# switching_board.net
KiCad netlist of a schematic drawn in Altium Designer
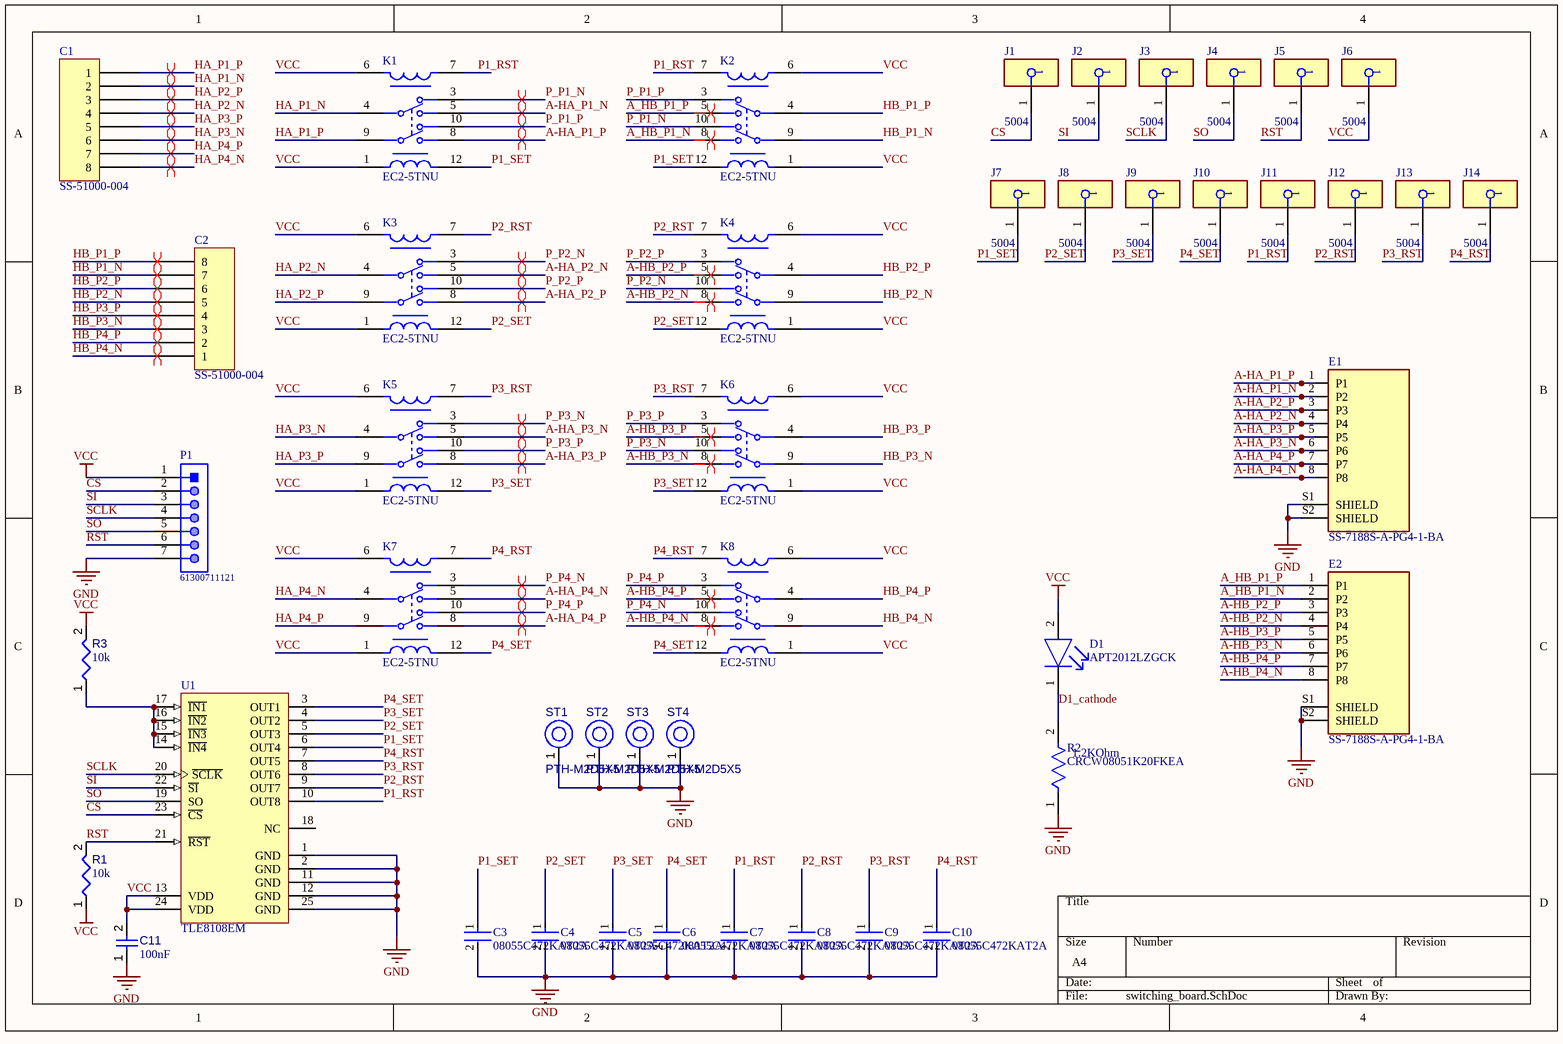
[diagram p0: switching_board.SchDoc]

(export (version "E")
  (design (tool "Eeschema 10.0.6"))
  (components
    (comp (ref "C1")
      (value "SS-51000-004")
      (footprint "SS-51000-004-Footprint-1")
      (description "Stewart Connector, Internal Part #: SS-51000-004")
      (libsource (lib "") (part "SS-51000-004-Symbol-1_1"))
    )
    (comp (ref "C2")
      (value "SS-51000-004")
      (footprint "SS-51000-004-Footprint-1")
      (description "Stewart Connector, Internal Part #: SS-51000-004")
      (libsource (lib "capstone") (part "SS-51000-004-Symbol-1"))
    )
    (comp (ref "C3")
      (value "08055C472KAT2A")
      (footprint "FP-0805-L_2_01_0_2-W_1_25-IPC_B")
      (description "General Purpose Ceramic Capacitor, 0805, 4.7nF, 10%, X7R, 0.15, 50V")
      (fields (field (name "VOLTAGE") "50V") (field (name "TOLERANCE") "10%"))
      (libsource (lib "Altium Content Vault") (part "02cd4be3c70576c341d710602a673aa"))
    )
    (comp (ref "C4")
      (value "08055C472KAT2A")
      (footprint "FP-0805-L_2_01_0_2-W_1_25-IPC_B")
      (description "General Purpose Ceramic Capacitor, 0805, 4.7nF, 10%, X7R, 0.15, 50V")
      (fields (field (name "VOLTAGE") "50V") (field (name "TOLERANCE") "10%"))
      (libsource (lib "Altium Content Vault") (part "02cd4be3c70576c341d710602a673aa"))
    )
    (comp (ref "C5")
      (value "08055C472KAT2A")
      (footprint "FP-0805-L_2_01_0_2-W_1_25-IPC_B")
      (description "General Purpose Ceramic Capacitor, 0805, 4.7nF, 10%, X7R, 0.15, 50V")
      (fields (field (name "VOLTAGE") "50V") (field (name "TOLERANCE") "10%"))
      (libsource (lib "Altium Content Vault") (part "02cd4be3c70576c341d710602a673aa"))
    )
    (comp (ref "C6")
      (value "08055C472KAT2A")
      (footprint "FP-0805-L_2_01_0_2-W_1_25-IPC_B")
      (description "General Purpose Ceramic Capacitor, 0805, 4.7nF, 10%, X7R, 0.15, 50V")
      (fields (field (name "VOLTAGE") "50V") (field (name "TOLERANCE") "10%"))
      (libsource (lib "Altium Content Vault") (part "02cd4be3c70576c341d710602a673aa"))
    )
    (comp (ref "C7")
      (value "08055C472KAT2A")
      (footprint "FP-0805-L_2_01_0_2-W_1_25-IPC_B")
      (description "General Purpose Ceramic Capacitor, 0805, 4.7nF, 10%, X7R, 0.15, 50V")
      (fields (field (name "VOLTAGE") "50V") (field (name "TOLERANCE") "10%"))
      (libsource (lib "Altium Content Vault") (part "02cd4be3c70576c341d710602a673aa"))
    )
    (comp (ref "C8")
      (value "08055C472KAT2A")
      (footprint "FP-0805-L_2_01_0_2-W_1_25-IPC_B")
      (description "General Purpose Ceramic Capacitor, 0805, 4.7nF, 10%, X7R, 0.15, 50V")
      (fields (field (name "VOLTAGE") "50V") (field (name "TOLERANCE") "10%"))
      (libsource (lib "Altium Content Vault") (part "02cd4be3c70576c341d710602a673aa"))
    )
    (comp (ref "C9")
      (value "08055C472KAT2A")
      (footprint "FP-0805-L_2_01_0_2-W_1_25-IPC_B")
      (description "General Purpose Ceramic Capacitor, 0805, 4.7nF, 10%, X7R, 0.15, 50V")
      (fields (field (name "VOLTAGE") "50V") (field (name "TOLERANCE") "10%"))
      (libsource (lib "Altium Content Vault") (part "02cd4be3c70576c341d710602a673aa"))
    )
    (comp (ref "C10")
      (value "08055C472KAT2A")
      (footprint "FP-0805-L_2_01_0_2-W_1_25-IPC_B")
      (description "General Purpose Ceramic Capacitor, 0805, 4.7nF, 10%, X7R, 0.15, 50V")
      (fields (field (name "VOLTAGE") "50V") (field (name "TOLERANCE") "10%"))
      (libsource (lib "Altium Content Vault") (part "02cd4be3c70576c341d710602a673aa"))
    )
    (comp (ref "C11")
      (value "100nF")
      (footprint "CAPC2013X95X50LL10T25")
      (description "Chip Capacitor, 100 nF, +/- 10%, 50 V, 0805 (2012 Metric)")
      (fields (field (name "TOLERANCE") "10%") (field (name "Comment") "Capacitor 100 nF +/-10% 50 V 0805"))
      (libsource (lib "capstone") (part "CAP-NP-2"))
    )
    (comp (ref "D1")
      (value "APT2012LZGCK")
      (footprint "FP-APT2012LZGCK-MFG")
      (description "LED GREEN CLEAR 2SMD")
      (libsource (lib "Altium Content Vault") (part "590121a5bdfd2d28d8ee457b77c7368"))
    )
    (comp (ref "E1")
      (value "SS-7188S-A-PG4-1-BA")
      (footprint "SS-7188S-A-PG4-1-BA-Footprint-1")
      (description "Conn Modular Jack F 8 POS 1.27mm Solder RA Thru-Hole 8 Terminal 1 Port")
      (libsource (lib "capstone") (part "SS-7188S-A-PG4-1-BA-Symbol-1"))
    )
    (comp (ref "E2")
      (value "SS-7188S-A-PG4-1-BA")
      (footprint "SS-7188S-A-PG4-1-BA-Footprint-1")
      (description "Conn Modular Jack F 8 POS 1.27mm Solder RA Thru-Hole 8 Terminal 1 Port")
      (libsource (lib "capstone") (part "SS-7188S-A-PG4-1-BA-Symbol-1"))
    )
    (comp (ref "J1")
      (value "5004")
      (footprint "FP-5004-MFG")
      (description "PC TEST POINT MINIATURE YELLOW")
      (fields
        (field (name "MANUFACTURER") "Keystone")
        (field (name "OCTOPART") "https://octopart.com/5004-keystone-28591")
      )
      (libsource (lib "Altium Content Vault") (part "98815daf2f2c152b0c43f5ab9800df6"))
    )
    (comp (ref "J2")
      (value "5004")
      (footprint "FP-5004-MFG")
      (description "PC TEST POINT MINIATURE YELLOW")
      (fields
        (field (name "MANUFACTURER") "Keystone")
        (field (name "OCTOPART") "https://octopart.com/5004-keystone-28591")
      )
      (libsource (lib "Altium Content Vault") (part "98815daf2f2c152b0c43f5ab9800df6"))
    )
    (comp (ref "J3")
      (value "5004")
      (footprint "FP-5004-MFG")
      (description "PC TEST POINT MINIATURE YELLOW")
      (fields
        (field (name "MANUFACTURER") "Keystone")
        (field (name "OCTOPART") "https://octopart.com/5004-keystone-28591")
      )
      (libsource (lib "Altium Content Vault") (part "98815daf2f2c152b0c43f5ab9800df6"))
    )
    (comp (ref "J4")
      (value "5004")
      (footprint "FP-5004-MFG")
      (description "PC TEST POINT MINIATURE YELLOW")
      (fields
        (field (name "MANUFACTURER") "Keystone")
        (field (name "OCTOPART") "https://octopart.com/5004-keystone-28591")
      )
      (libsource (lib "Altium Content Vault") (part "98815daf2f2c152b0c43f5ab9800df6"))
    )
    (comp (ref "J5")
      (value "5004")
      (footprint "FP-5004-MFG")
      (description "PC TEST POINT MINIATURE YELLOW")
      (fields
        (field (name "MANUFACTURER") "Keystone")
        (field (name "OCTOPART") "https://octopart.com/5004-keystone-28591")
      )
      (libsource (lib "Altium Content Vault") (part "98815daf2f2c152b0c43f5ab9800df6"))
    )
    (comp (ref "J6")
      (value "5004")
      (footprint "FP-5004-MFG")
      (description "PC TEST POINT MINIATURE YELLOW")
      (fields
        (field (name "MANUFACTURER") "Keystone")
        (field (name "OCTOPART") "https://octopart.com/5004-keystone-28591")
      )
      (libsource (lib "Altium Content Vault") (part "98815daf2f2c152b0c43f5ab9800df6"))
    )
    (comp (ref "J7")
      (value "5004")
      (footprint "FP-5004-MFG")
      (description "PC TEST POINT MINIATURE YELLOW")
      (fields
        (field (name "MANUFACTURER") "Keystone")
        (field (name "OCTOPART") "https://octopart.com/5004-keystone-28591")
      )
      (libsource (lib "Altium Content Vault") (part "98815daf2f2c152b0c43f5ab9800df6"))
    )
    (comp (ref "J8")
      (value "5004")
      (footprint "FP-5004-MFG")
      (description "PC TEST POINT MINIATURE YELLOW")
      (fields
        (field (name "MANUFACTURER") "Keystone")
        (field (name "OCTOPART") "https://octopart.com/5004-keystone-28591")
      )
      (libsource (lib "Altium Content Vault") (part "98815daf2f2c152b0c43f5ab9800df6"))
    )
    (comp (ref "J9")
      (value "5004")
      (footprint "FP-5004-MFG")
      (description "PC TEST POINT MINIATURE YELLOW")
      (fields
        (field (name "MANUFACTURER") "Keystone")
        (field (name "OCTOPART") "https://octopart.com/5004-keystone-28591")
      )
      (libsource (lib "Altium Content Vault") (part "98815daf2f2c152b0c43f5ab9800df6"))
    )
    (comp (ref "J10")
      (value "5004")
      (footprint "FP-5004-MFG")
      (description "PC TEST POINT MINIATURE YELLOW")
      (fields
        (field (name "MANUFACTURER") "Keystone")
        (field (name "OCTOPART") "https://octopart.com/5004-keystone-28591")
      )
      (libsource (lib "Altium Content Vault") (part "98815daf2f2c152b0c43f5ab9800df6"))
    )
    (comp (ref "J11")
      (value "5004")
      (footprint "FP-5004-MFG")
      (description "PC TEST POINT MINIATURE YELLOW")
      (fields
        (field (name "MANUFACTURER") "Keystone")
        (field (name "OCTOPART") "https://octopart.com/5004-keystone-28591")
      )
      (libsource (lib "Altium Content Vault") (part "98815daf2f2c152b0c43f5ab9800df6"))
    )
    (comp (ref "J12")
      (value "5004")
      (footprint "FP-5004-MFG")
      (description "PC TEST POINT MINIATURE YELLOW")
      (fields
        (field (name "MANUFACTURER") "Keystone")
        (field (name "OCTOPART") "https://octopart.com/5004-keystone-28591")
      )
      (libsource (lib "Altium Content Vault") (part "98815daf2f2c152b0c43f5ab9800df6"))
    )
    (comp (ref "J13")
      (value "5004")
      (footprint "FP-5004-MFG")
      (description "PC TEST POINT MINIATURE YELLOW")
      (fields
        (field (name "MANUFACTURER") "Keystone")
        (field (name "OCTOPART") "https://octopart.com/5004-keystone-28591")
      )
      (libsource (lib "Altium Content Vault") (part "98815daf2f2c152b0c43f5ab9800df6"))
    )
    (comp (ref "J14")
      (value "5004")
      (footprint "FP-5004-MFG")
      (description "PC TEST POINT MINIATURE YELLOW")
      (fields
        (field (name "MANUFACTURER") "Keystone")
        (field (name "OCTOPART") "https://octopart.com/5004-keystone-28591")
      )
      (libsource (lib "Altium Content Vault") (part "98815daf2f2c152b0c43f5ab9800df6"))
    )
    (comp (ref "K1")
      (value "EC2-5TNU")
      (footprint "FP-EC2-5TNU-MFG")
      (description "RELAY GEN PURPOSE DPDT 2A 5VDC")
      (libsource (lib "") (part "760bddf1a8497dee72f3acbcfdb9cd1_1"))
    )
    (comp (ref "K2")
      (value "EC2-5TNU")
      (footprint "FP-EC2-5TNU-MFG")
      (description "RELAY GEN PURPOSE DPDT 2A 5VDC")
      (libsource (lib "Altium Content Vault") (part "760bddf1a8497dee72f3acbcfdb9cd1"))
    )
    (comp (ref "K3")
      (value "EC2-5TNU")
      (footprint "FP-EC2-5TNU-MFG")
      (description "RELAY GEN PURPOSE DPDT 2A 5VDC")
      (libsource (lib "") (part "760bddf1a8497dee72f3acbcfdb9cd1_1"))
    )
    (comp (ref "K4")
      (value "EC2-5TNU")
      (footprint "FP-EC2-5TNU-MFG")
      (description "RELAY GEN PURPOSE DPDT 2A 5VDC")
      (libsource (lib "Altium Content Vault") (part "760bddf1a8497dee72f3acbcfdb9cd1"))
    )
    (comp (ref "K5")
      (value "EC2-5TNU")
      (footprint "FP-EC2-5TNU-MFG")
      (description "RELAY GEN PURPOSE DPDT 2A 5VDC")
      (libsource (lib "") (part "760bddf1a8497dee72f3acbcfdb9cd1_1"))
    )
    (comp (ref "K6")
      (value "EC2-5TNU")
      (footprint "FP-EC2-5TNU-MFG")
      (description "RELAY GEN PURPOSE DPDT 2A 5VDC")
      (libsource (lib "Altium Content Vault") (part "760bddf1a8497dee72f3acbcfdb9cd1"))
    )
    (comp (ref "K7")
      (value "EC2-5TNU")
      (footprint "FP-EC2-5TNU-MFG")
      (description "RELAY GEN PURPOSE DPDT 2A 5VDC")
      (libsource (lib "") (part "760bddf1a8497dee72f3acbcfdb9cd1_1"))
    )
    (comp (ref "K8")
      (value "EC2-5TNU")
      (footprint "FP-EC2-5TNU-MFG")
      (description "RELAY GEN PURPOSE DPDT 2A 5VDC")
      (libsource (lib "Altium Content Vault") (part "760bddf1a8497dee72f3acbcfdb9cd1"))
    )
    (comp (ref "P1")
      (value "61300711121")
      (footprint "61300711121")
      (description "THT Vertical Pin Header WR-PHD, Pitch 2.54 mm, Single Row, 7 pins")
      (fields (field (name "MANUFACTURER") "Wurth Elektronik") (field (name "PUBLISHER") "WurthElektronik"))
      (libsource (lib "Altium Content Vault") (part "WE-CN-1P-M-R7"))
    )
    (comp (ref "R1")
      (value "10k")
      (footprint "RESC2013X50X35ML15T15")
      (description "Chip Resistor, 10 KOhm, +/- 1%, 125 mW, -55 to 155 degC, 0805 (2012 Metric)")
      (fields (field (name "TOLERANCE") "1%") (field (name "POWER") "125mW"))
      (libsource (lib "capstone") (part "RES-2"))
    )
    (comp (ref "R2")
      (value "CRCW08051K20FKEA")
      (footprint "FP-CRCW0805-e3-MFG")
      (description "RES Thick Film, 1.2kΩ, 1%, 0.125W, 100ppm/°C, 0805")
      (fields (field (name "TOLERANCE") "1%"))
      (libsource (lib "Altium Content Vault") (part "1029c3af85768c4190bb7ad29bc67b5"))
    )
    (comp (ref "R3")
      (value "10k")
      (footprint "RESC2013X50X35ML15T15")
      (description "Chip Resistor, 10 KOhm, +/- 1%, 125 mW, -55 to 155 degC, 0805 (2012 Metric)")
      (fields (field (name "TOLERANCE") "1%") (field (name "POWER") "125mW"))
      (libsource (lib "capstone") (part "RES-2"))
    )
    (comp (ref "ST1")
      (value "PTH-M2D5X5")
      (footprint "PTH-M2D5X5")
      (description "M2 PTH (2.5mm), 5mm pad")
      (libsource (lib "capstone") (part "CMP-00028-00000-1"))
    )
    (comp (ref "ST2")
      (value "PTH-M2D5X5")
      (footprint "PTH-M2D5X5")
      (description "M2 PTH (2.5mm), 5mm pad")
      (libsource (lib "capstone") (part "CMP-00028-00000-1"))
    )
    (comp (ref "ST3")
      (value "PTH-M2D5X5")
      (footprint "PTH-M2D5X5")
      (description "M2 PTH (2.5mm), 5mm pad")
      (libsource (lib "capstone") (part "CMP-00028-00000-1"))
    )
    (comp (ref "ST4")
      (value "PTH-M2D5X5")
      (footprint "PTH-M2D5X5")
      (description "M2 PTH (2.5mm), 5mm pad")
      (libsource (lib "capstone") (part "CMP-00028-00000-1"))
    )
    (comp (ref "U1")
      (value "TLE8108EM")
      (footprint "INF-PG-SSOP-24-4_L")
      (fields (field (name "MANUFACTURER") "Infineon"))
      (libsource (lib "Altium Content Vault") (part "INF-TLE8108EM-PG-SSOP-24-4-24"))
    )
  )
  (nets
    (net (code "1") (name "/A-HA_P1_N") (class "Default")
      (node (ref "E1") (pin "2") (pinfunction "P2_2") (pintype "passive"))
      (node (ref "K1") (pin "5") (pinfunction "5_5") (pintype "passive"))
    )
    (net (code "2") (name "/A-HA_P1_P") (class "Default")
      (node (ref "E1") (pin "1") (pinfunction "P1_1") (pintype "passive"))
      (node (ref "K1") (pin "8") (pinfunction "8_8") (pintype "passive"))
    )
    (net (code "3") (name "/A-HA_P2_N") (class "Default")
      (node (ref "E1") (pin "4") (pinfunction "P4_4") (pintype "passive"))
      (node (ref "K3") (pin "5") (pinfunction "5_5") (pintype "passive"))
    )
    (net (code "4") (name "/A-HA_P2_P") (class "Default")
      (node (ref "E1") (pin "3") (pinfunction "P3_3") (pintype "passive"))
      (node (ref "K3") (pin "8") (pinfunction "8_8") (pintype "passive"))
    )
    (net (code "5") (name "/A-HA_P3_N") (class "Default")
      (node (ref "E1") (pin "6") (pinfunction "P6_6") (pintype "passive"))
      (node (ref "K5") (pin "5") (pinfunction "5_5") (pintype "passive"))
    )
    (net (code "6") (name "/A-HA_P3_P") (class "Default")
      (node (ref "E1") (pin "5") (pinfunction "P5_5") (pintype "passive"))
      (node (ref "K5") (pin "8") (pinfunction "8_8") (pintype "passive"))
    )
    (net (code "7") (name "/A-HA_P4_N") (class "Default")
      (node (ref "E1") (pin "8") (pinfunction "P8_8") (pintype "passive"))
      (node (ref "K7") (pin "5") (pinfunction "5_5") (pintype "passive"))
    )
    (net (code "8") (name "/A-HA_P4_P") (class "Default")
      (node (ref "E1") (pin "7") (pinfunction "P7_7") (pintype "passive"))
      (node (ref "K7") (pin "8") (pinfunction "8_8") (pintype "passive"))
    )
    (net (code "9") (name "/A-HB_P2_N") (class "Default")
      (node (ref "E2") (pin "4") (pinfunction "P4_4") (pintype "passive"))
      (node (ref "K4") (pin "8") (pinfunction "8_8") (pintype "passive"))
    )
    (net (code "10") (name "/A-HB_P2_P") (class "Default")
      (node (ref "E2") (pin "3") (pinfunction "P3_3") (pintype "passive"))
      (node (ref "K4") (pin "5") (pinfunction "5_5") (pintype "passive"))
    )
    (net (code "11") (name "/A-HB_P3_N") (class "Default")
      (node (ref "E2") (pin "6") (pinfunction "P6_6") (pintype "passive"))
      (node (ref "K6") (pin "8") (pinfunction "8_8") (pintype "passive"))
    )
    (net (code "12") (name "/A-HB_P3_P") (class "Default")
      (node (ref "E2") (pin "5") (pinfunction "P5_5") (pintype "passive"))
      (node (ref "K6") (pin "5") (pinfunction "5_5") (pintype "passive"))
    )
    (net (code "13") (name "/A-HB_P4_N") (class "Default")
      (node (ref "E2") (pin "8") (pinfunction "P8_8") (pintype "passive"))
      (node (ref "K8") (pin "8") (pinfunction "8_8") (pintype "passive"))
    )
    (net (code "14") (name "/A-HB_P4_P") (class "Default")
      (node (ref "E2") (pin "7") (pinfunction "P7_7") (pintype "passive"))
      (node (ref "K8") (pin "5") (pinfunction "5_5") (pintype "passive"))
    )
    (net (code "15") (name "/A_HB_P1_N") (class "Default")
      (node (ref "E2") (pin "2") (pinfunction "P2_2") (pintype "passive"))
      (node (ref "K2") (pin "8") (pinfunction "8_8") (pintype "passive"))
    )
    (net (code "16") (name "/A_HB_P1_P") (class "Default")
      (node (ref "E2") (pin "1") (pinfunction "P1_1") (pintype "passive"))
      (node (ref "K2") (pin "5") (pinfunction "5_5") (pintype "passive"))
    )
    (net (code "17") (name "/CS") (class "Default")
      (node (ref "J1") (pin "1") (pinfunction "1_1") (pintype "passive"))
      (node (ref "P1") (pin "2") (pinfunction "2_2") (pintype "passive"))
      (node (ref "U1") (pin "23") (pinfunction "~{CS}_23") (pintype "input"))
    )
    (net (code "18") (name "/D1_cathode") (class "Default")
      (node (ref "D1") (pin "1") (pinfunction "C_1") (pintype "passive"))
      (node (ref "R2") (pin "2") (pinfunction "2_2") (pintype "passive"))
    )
    (net (code "19") (name "/HA_P1_N") (class "Default")
      (node (ref "C1") (pin "2") (pinfunction "2_2") (pintype "passive"))
      (node (ref "K1") (pin "4") (pinfunction "4_4") (pintype "passive"))
    )
    (net (code "20") (name "/HA_P1_P") (class "Default")
      (node (ref "C1") (pin "1") (pinfunction "1_1") (pintype "passive"))
      (node (ref "K1") (pin "9") (pinfunction "9_9") (pintype "passive"))
    )
    (net (code "21") (name "/HA_P2_N") (class "Default")
      (node (ref "C1") (pin "4") (pinfunction "4_4") (pintype "passive"))
      (node (ref "K3") (pin "4") (pinfunction "4_4") (pintype "passive"))
    )
    (net (code "22") (name "/HA_P2_P") (class "Default")
      (node (ref "C1") (pin "3") (pinfunction "3_3") (pintype "passive"))
      (node (ref "K3") (pin "9") (pinfunction "9_9") (pintype "passive"))
    )
    (net (code "23") (name "/HA_P3_N") (class "Default")
      (node (ref "C1") (pin "6") (pinfunction "6_6") (pintype "passive"))
      (node (ref "K5") (pin "4") (pinfunction "4_4") (pintype "passive"))
    )
    (net (code "24") (name "/HA_P3_P") (class "Default")
      (node (ref "C1") (pin "5") (pinfunction "5_5") (pintype "passive"))
      (node (ref "K5") (pin "9") (pinfunction "9_9") (pintype "passive"))
    )
    (net (code "25") (name "/HA_P4_N") (class "Default")
      (node (ref "C1") (pin "8") (pinfunction "8_8") (pintype "passive"))
      (node (ref "K7") (pin "4") (pinfunction "4_4") (pintype "passive"))
    )
    (net (code "26") (name "/HA_P4_P") (class "Default")
      (node (ref "C1") (pin "7") (pinfunction "7_7") (pintype "passive"))
      (node (ref "K7") (pin "9") (pinfunction "9_9") (pintype "passive"))
    )
    (net (code "27") (name "/HB_P1_N") (class "Default")
      (node (ref "C2") (pin "7") (pinfunction "7_7") (pintype "passive"))
      (node (ref "K2") (pin "9") (pinfunction "9_9") (pintype "passive"))
    )
    (net (code "28") (name "/HB_P1_P") (class "Default")
      (node (ref "C2") (pin "8") (pinfunction "8_8") (pintype "passive"))
      (node (ref "K2") (pin "4") (pinfunction "4_4") (pintype "passive"))
    )
    (net (code "29") (name "/HB_P2_N") (class "Default")
      (node (ref "C2") (pin "5") (pinfunction "5_5") (pintype "passive"))
      (node (ref "K4") (pin "9") (pinfunction "9_9") (pintype "passive"))
    )
    (net (code "30") (name "/HB_P2_P") (class "Default")
      (node (ref "C2") (pin "6") (pinfunction "6_6") (pintype "passive"))
      (node (ref "K4") (pin "4") (pinfunction "4_4") (pintype "passive"))
    )
    (net (code "31") (name "/HB_P3_N") (class "Default")
      (node (ref "C2") (pin "3") (pinfunction "3_3") (pintype "passive"))
      (node (ref "K6") (pin "9") (pinfunction "9_9") (pintype "passive"))
    )
    (net (code "32") (name "/HB_P3_P") (class "Default")
      (node (ref "C2") (pin "4") (pinfunction "4_4") (pintype "passive"))
      (node (ref "K6") (pin "4") (pinfunction "4_4") (pintype "passive"))
    )
    (net (code "33") (name "/HB_P4_N") (class "Default")
      (node (ref "C2") (pin "1") (pinfunction "1_1") (pintype "passive"))
      (node (ref "K8") (pin "9") (pinfunction "9_9") (pintype "passive"))
    )
    (net (code "34") (name "/HB_P4_P") (class "Default")
      (node (ref "C2") (pin "2") (pinfunction "2_2") (pintype "passive"))
      (node (ref "K8") (pin "4") (pinfunction "4_4") (pintype "passive"))
    )
    (net (code "35") (name "/P1_RST") (class "Default")
      (node (ref "C7") (pin "1") (pinfunction "1_1") (pintype "passive"))
      (node (ref "J11") (pin "1") (pinfunction "1_1") (pintype "passive"))
      (node (ref "K1") (pin "7") (pinfunction "R-_7") (pintype "passive"))
      (node (ref "K2") (pin "7") (pinfunction "R-_7") (pintype "passive"))
      (node (ref "U1") (pin "10") (pinfunction "OUT8_10") (pintype "power_in"))
    )
    (net (code "36") (name "/P1_SET") (class "Default")
      (node (ref "C3") (pin "1") (pinfunction "1_1") (pintype "passive"))
      (node (ref "J7") (pin "1") (pinfunction "1_1") (pintype "passive"))
      (node (ref "K1") (pin "12") (pinfunction "S-_12") (pintype "passive"))
      (node (ref "K2") (pin "12") (pinfunction "S-_12") (pintype "passive"))
      (node (ref "U1") (pin "6") (pinfunction "OUT4_6") (pintype "power_in"))
    )
    (net (code "37") (name "/P2_RST") (class "Default")
      (node (ref "C8") (pin "1") (pinfunction "1_1") (pintype "passive"))
      (node (ref "J12") (pin "1") (pinfunction "1_1") (pintype "passive"))
      (node (ref "K3") (pin "7") (pinfunction "R-_7") (pintype "passive"))
      (node (ref "K4") (pin "7") (pinfunction "R-_7") (pintype "passive"))
      (node (ref "U1") (pin "9") (pinfunction "OUT7_9") (pintype "power_in"))
    )
    (net (code "38") (name "/P2_SET") (class "Default")
      (node (ref "C4") (pin "1") (pinfunction "1_1") (pintype "passive"))
      (node (ref "J8") (pin "1") (pinfunction "1_1") (pintype "passive"))
      (node (ref "K3") (pin "12") (pinfunction "S-_12") (pintype "passive"))
      (node (ref "K4") (pin "12") (pinfunction "S-_12") (pintype "passive"))
      (node (ref "U1") (pin "5") (pinfunction "OUT3_5") (pintype "power_in"))
    )
    (net (code "39") (name "/P3_RST") (class "Default")
      (node (ref "C9") (pin "1") (pinfunction "1_1") (pintype "passive"))
      (node (ref "J13") (pin "1") (pinfunction "1_1") (pintype "passive"))
      (node (ref "K5") (pin "7") (pinfunction "R-_7") (pintype "passive"))
      (node (ref "K6") (pin "7") (pinfunction "R-_7") (pintype "passive"))
      (node (ref "U1") (pin "8") (pinfunction "OUT6_8") (pintype "power_in"))
    )
    (net (code "40") (name "/P3_SET") (class "Default")
      (node (ref "C5") (pin "1") (pinfunction "1_1") (pintype "passive"))
      (node (ref "J9") (pin "1") (pinfunction "1_1") (pintype "passive"))
      (node (ref "K5") (pin "12") (pinfunction "S-_12") (pintype "passive"))
      (node (ref "K6") (pin "12") (pinfunction "S-_12") (pintype "passive"))
      (node (ref "U1") (pin "4") (pinfunction "OUT2_4") (pintype "power_in"))
    )
    (net (code "41") (name "/P4_RST") (class "Default")
      (node (ref "C10") (pin "1") (pinfunction "1_1") (pintype "passive"))
      (node (ref "J14") (pin "1") (pinfunction "1_1") (pintype "passive"))
      (node (ref "K7") (pin "7") (pinfunction "R-_7") (pintype "passive"))
      (node (ref "K8") (pin "7") (pinfunction "R-_7") (pintype "passive"))
      (node (ref "U1") (pin "7") (pinfunction "OUT5_7") (pintype "power_in"))
    )
    (net (code "42") (name "/P4_SET") (class "Default")
      (node (ref "C6") (pin "1") (pinfunction "1_1") (pintype "passive"))
      (node (ref "J10") (pin "1") (pinfunction "1_1") (pintype "passive"))
      (node (ref "K7") (pin "12") (pinfunction "S-_12") (pintype "passive"))
      (node (ref "K8") (pin "12") (pinfunction "S-_12") (pintype "passive"))
      (node (ref "U1") (pin "3") (pinfunction "OUT1_3") (pintype "power_in"))
    )
    (net (code "43") (name "/P_P1_N") (class "Default")
      (node (ref "K1") (pin "3") (pinfunction "3_3") (pintype "passive"))
      (node (ref "K2") (pin "10") (pinfunction "10_10") (pintype "passive"))
    )
    (net (code "44") (name "/P_P1_P") (class "Default")
      (node (ref "K1") (pin "10") (pinfunction "10_10") (pintype "passive"))
      (node (ref "K2") (pin "3") (pinfunction "3_3") (pintype "passive"))
    )
    (net (code "45") (name "/P_P2_N") (class "Default")
      (node (ref "K3") (pin "3") (pinfunction "3_3") (pintype "passive"))
      (node (ref "K4") (pin "10") (pinfunction "10_10") (pintype "passive"))
    )
    (net (code "46") (name "/P_P2_P") (class "Default")
      (node (ref "K3") (pin "10") (pinfunction "10_10") (pintype "passive"))
      (node (ref "K4") (pin "3") (pinfunction "3_3") (pintype "passive"))
    )
    (net (code "47") (name "/P_P3_N") (class "Default")
      (node (ref "K5") (pin "3") (pinfunction "3_3") (pintype "passive"))
      (node (ref "K6") (pin "10") (pinfunction "10_10") (pintype "passive"))
    )
    (net (code "48") (name "/P_P3_P") (class "Default")
      (node (ref "K5") (pin "10") (pinfunction "10_10") (pintype "passive"))
      (node (ref "K6") (pin "3") (pinfunction "3_3") (pintype "passive"))
    )
    (net (code "49") (name "/P_P4_N") (class "Default")
      (node (ref "K7") (pin "3") (pinfunction "3_3") (pintype "passive"))
      (node (ref "K8") (pin "10") (pinfunction "10_10") (pintype "passive"))
    )
    (net (code "50") (name "/P_P4_P") (class "Default")
      (node (ref "K7") (pin "10") (pinfunction "10_10") (pintype "passive"))
      (node (ref "K8") (pin "3") (pinfunction "3_3") (pintype "passive"))
    )
    (net (code "51") (name "/RST") (class "Default")
      (node (ref "J5") (pin "1") (pinfunction "1_1") (pintype "passive"))
      (node (ref "P1") (pin "6") (pinfunction "6_6") (pintype "passive"))
      (node (ref "R1") (pin "2") (pinfunction "2_2") (pintype "passive"))
      (node (ref "U1") (pin "21") (pinfunction "~{RST}_21") (pintype "input"))
    )
    (net (code "52") (name "/SCLK") (class "Default")
      (node (ref "J3") (pin "1") (pinfunction "1_1") (pintype "passive"))
      (node (ref "P1") (pin "4") (pinfunction "4_4") (pintype "passive"))
      (node (ref "U1") (pin "20") (pinfunction "~{SCLK}_20") (pintype "input"))
    )
    (net (code "53") (name "/SI") (class "Default")
      (node (ref "J2") (pin "1") (pinfunction "1_1") (pintype "passive"))
      (node (ref "P1") (pin "3") (pinfunction "3_3") (pintype "passive"))
      (node (ref "U1") (pin "22") (pinfunction "~{SI}_22") (pintype "input"))
    )
    (net (code "54") (name "/SO") (class "Default")
      (node (ref "J4") (pin "1") (pinfunction "1_1") (pintype "passive"))
      (node (ref "P1") (pin "5") (pinfunction "5_5") (pintype "passive"))
      (node (ref "U1") (pin "19") (pinfunction "SO_19") (pintype "tri_state"))
    )
    (net (code "55") (name "GND") (class "Default")
      (node (ref "C10") (pin "2") (pinfunction "2_2") (pintype "passive"))
      (node (ref "C11") (pin "1") (pinfunction "1_1") (pintype "passive"))
      (node (ref "C3") (pin "2") (pinfunction "2_2") (pintype "passive"))
      (node (ref "C4") (pin "2") (pinfunction "2_2") (pintype "passive"))
      (node (ref "C5") (pin "2") (pinfunction "2_2") (pintype "passive"))
      (node (ref "C6") (pin "2") (pinfunction "2_2") (pintype "passive"))
      (node (ref "C7") (pin "2") (pinfunction "2_2") (pintype "passive"))
      (node (ref "C8") (pin "2") (pinfunction "2_2") (pintype "passive"))
      (node (ref "C9") (pin "2") (pinfunction "2_2") (pintype "passive"))
      (node (ref "E1") (pin "S1") (pinfunction "SHIELD_S1") (pintype "passive"))
      (node (ref "E1") (pin "S2") (pinfunction "SHIELD_S2") (pintype "passive"))
      (node (ref "E2") (pin "S1") (pinfunction "SHIELD_S1") (pintype "passive"))
      (node (ref "E2") (pin "S2") (pinfunction "SHIELD_S2") (pintype "passive"))
      (node (ref "P1") (pin "7") (pinfunction "7_7") (pintype "passive"))
      (node (ref "R2") (pin "1") (pinfunction "1_1") (pintype "passive"))
      (node (ref "ST1") (pin "1") (pinfunction "H1_1") (pintype "passive"))
      (node (ref "ST2") (pin "1") (pinfunction "H1_1") (pintype "passive"))
      (node (ref "ST3") (pin "1") (pinfunction "H1_1") (pintype "passive"))
      (node (ref "ST4") (pin "1") (pinfunction "H1_1") (pintype "passive"))
      (node (ref "U1") (pin "1") (pinfunction "GND_1") (pintype "power_in"))
      (node (ref "U1") (pin "11") (pinfunction "GND_11") (pintype "power_in"))
      (node (ref "U1") (pin "12") (pinfunction "GND_12") (pintype "power_in"))
      (node (ref "U1") (pin "2") (pinfunction "GND_2") (pintype "power_in"))
      (node (ref "U1") (pin "25") (pinfunction "GND_25") (pintype "power_in"))
    )
    (net (code "56") (name "Net-(U1-~{IN1})") (class "Default")
      (node (ref "R3") (pin "1") (pinfunction "1_1") (pintype "passive"))
      (node (ref "U1") (pin "14") (pinfunction "~{IN4}_14") (pintype "input"))
      (node (ref "U1") (pin "15") (pinfunction "~{IN3}_15") (pintype "input"))
      (node (ref "U1") (pin "16") (pinfunction "~{IN2}_16") (pintype "input"))
      (node (ref "U1") (pin "17") (pinfunction "~{IN1}_17") (pintype "input"))
    )
    (net (code "57") (name "VCC") (class "Default")
      (node (ref "C11") (pin "2") (pinfunction "2_2") (pintype "passive"))
      (node (ref "D1") (pin "2") (pinfunction "A_2") (pintype "passive"))
      (node (ref "J6") (pin "1") (pinfunction "1_1") (pintype "passive"))
      (node (ref "K1") (pin "1") (pinfunction "S+_1") (pintype "passive"))
      (node (ref "K1") (pin "6") (pinfunction "R+_6") (pintype "passive"))
      (node (ref "K2") (pin "1") (pinfunction "S+_1") (pintype "passive"))
      (node (ref "K2") (pin "6") (pinfunction "R+_6") (pintype "passive"))
      (node (ref "K3") (pin "1") (pinfunction "S+_1") (pintype "passive"))
      (node (ref "K3") (pin "6") (pinfunction "R+_6") (pintype "passive"))
      (node (ref "K4") (pin "1") (pinfunction "S+_1") (pintype "passive"))
      (node (ref "K4") (pin "6") (pinfunction "R+_6") (pintype "passive"))
      (node (ref "K5") (pin "1") (pinfunction "S+_1") (pintype "passive"))
      (node (ref "K5") (pin "6") (pinfunction "R+_6") (pintype "passive"))
      (node (ref "K6") (pin "1") (pinfunction "S+_1") (pintype "passive"))
      (node (ref "K6") (pin "6") (pinfunction "R+_6") (pintype "passive"))
      (node (ref "K7") (pin "1") (pinfunction "S+_1") (pintype "passive"))
      (node (ref "K7") (pin "6") (pinfunction "R+_6") (pintype "passive"))
      (node (ref "K8") (pin "1") (pinfunction "S+_1") (pintype "passive"))
      (node (ref "K8") (pin "6") (pinfunction "R+_6") (pintype "passive"))
      (node (ref "P1") (pin "1") (pinfunction "1_1") (pintype "passive"))
      (node (ref "R1") (pin "1") (pinfunction "1_1") (pintype "passive"))
      (node (ref "R3") (pin "2") (pinfunction "2_2") (pintype "passive"))
      (node (ref "U1") (pin "13") (pinfunction "VDD_13") (pintype "power_in"))
      (node (ref "U1") (pin "24") (pinfunction "VDD_24") (pintype "power_in"))
    )
    (net (code "58") (name "unconnected-(U1-NC-Pad18)") (class "Default")
      (node (ref "U1") (pin "18") (pinfunction "NC_18") (pintype "passive"))
    )
  )
)
